# pwr.net
KiCad netlist of a schematic drawn in EAGLE
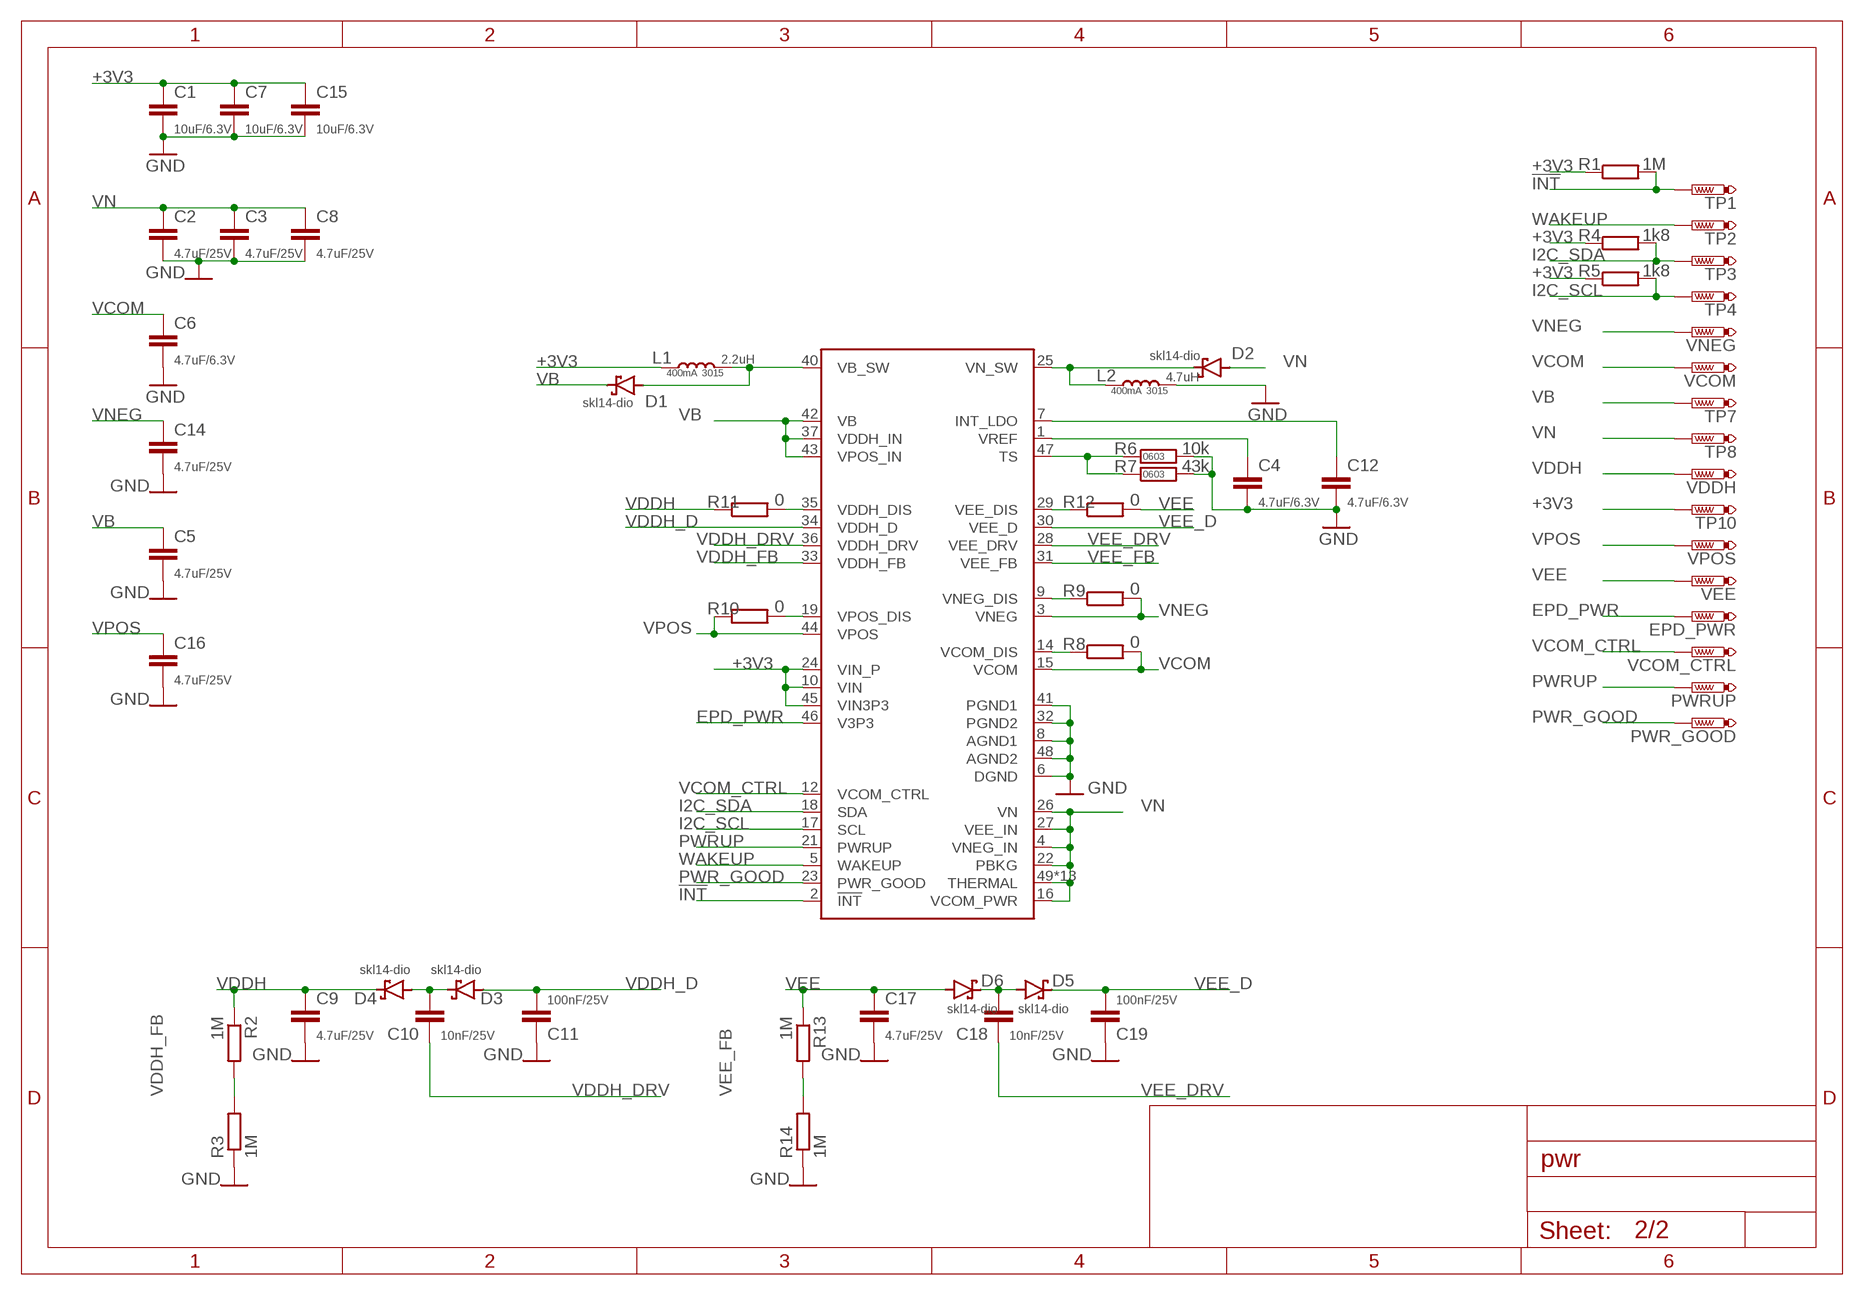
[diagram p0: schematic, sheet 2]

(export (version "E")
  (design (tool "Eeschema 10.0.6"))
  (components
    (comp (ref "C1")
      (value "10uF/6.3V")
      (footprint "eagle-import:C0805")
      (libsource (lib "eagle-import") (part "C-EUC0805"))
    )
    (comp (ref "C2")
      (value "4.7uF/25V")
      (footprint "eagle-import:C0805")
      (libsource (lib "eagle-import") (part "C-EUC0805"))
    )
    (comp (ref "C3")
      (value "4.7uF/25V")
      (footprint "eagle-import:C0805")
      (libsource (lib "eagle-import") (part "C-EUC0805"))
    )
    (comp (ref "C4")
      (value "4.7uF/6.3V")
      (footprint "eagle-import:C0603")
      (libsource (lib "eagle-import") (part "C-EUC0603"))
    )
    (comp (ref "C5")
      (value "4.7uF/25V")
      (footprint "eagle-import:C0805")
      (libsource (lib "eagle-import") (part "C-EUC0805"))
    )
    (comp (ref "C6")
      (value "4.7uF/6.3V")
      (footprint "eagle-import:C0603")
      (libsource (lib "eagle-import") (part "C-EUC0603"))
    )
    (comp (ref "C7")
      (value "10uF/6.3V")
      (footprint "eagle-import:C0805")
      (libsource (lib "eagle-import") (part "C-EUC0805"))
    )
    (comp (ref "C8")
      (value "4.7uF/25V")
      (footprint "eagle-import:C0805")
      (libsource (lib "eagle-import") (part "C-EUC0805"))
    )
    (comp (ref "C9")
      (value "4.7uF/25V")
      (footprint "eagle-import:C0805")
      (libsource (lib "eagle-import") (part "C-EUC0805"))
    )
    (comp (ref "C10")
      (value "10nF/25V")
      (footprint "eagle-import:C0402")
      (libsource (lib "eagle-import") (part "C-EUC0402"))
    )
    (comp (ref "C11")
      (value "100nF/25V")
      (footprint "eagle-import:C0603")
      (libsource (lib "eagle-import") (part "C-EUC0603"))
    )
    (comp (ref "C12")
      (value "4.7uF/6.3V")
      (footprint "eagle-import:C0603")
      (libsource (lib "eagle-import") (part "C-EUC0603"))
    )
    (comp (ref "C14")
      (value "4.7uF/25V")
      (footprint "eagle-import:C0805")
      (libsource (lib "eagle-import") (part "C-EUC0805"))
    )
    (comp (ref "C15")
      (value "10uF/6.3V")
      (footprint "eagle-import:C0805")
      (libsource (lib "eagle-import") (part "C-EUC0805"))
    )
    (comp (ref "C16")
      (value "4.7uF/25V")
      (footprint "eagle-import:C0805")
      (libsource (lib "eagle-import") (part "C-EUC0805"))
    )
    (comp (ref "C17")
      (value "4.7uF/25V")
      (footprint "eagle-import:C0805")
      (libsource (lib "eagle-import") (part "C-EUC0805"))
    )
    (comp (ref "C18")
      (value "10nF/25V")
      (footprint "eagle-import:C0402")
      (libsource (lib "eagle-import") (part "C-EUC0402"))
    )
    (comp (ref "C19")
      (value "100nF/25V")
      (footprint "eagle-import:C0603")
      (libsource (lib "eagle-import") (part "C-EUC0603"))
    )
    (comp (ref "D1")
      (value "skl14-dio")
      (footprint "eagle-import:SODFL3718X130")
      (libsource (lib "eagle-import") (part "SKL14"))
    )
    (comp (ref "D2")
      (value "skl14-dio")
      (footprint "eagle-import:SODFL3718X130")
      (libsource (lib "eagle-import") (part "SKL14"))
    )
    (comp (ref "D3")
      (value "skl14-dio")
      (footprint "eagle-import:SODFL3718X130")
      (libsource (lib "eagle-import") (part "SKL14"))
    )
    (comp (ref "D4")
      (value "skl14-dio")
      (footprint "eagle-import:SODFL3718X130")
      (libsource (lib "eagle-import") (part "SKL14"))
    )
    (comp (ref "D5")
      (value "skl14-dio")
      (footprint "eagle-import:SODFL3718X130")
      (libsource (lib "eagle-import") (part "SKL14"))
    )
    (comp (ref "D6")
      (value "skl14-dio")
      (footprint "eagle-import:SODFL3718X130")
      (libsource (lib "eagle-import") (part "SKL14"))
    )
    (comp (ref "EPD_PWR")
      (value "PTR1B1,27")
      (footprint "eagle-import:B1,27")
      (libsource (lib "eagle-import") (part "PTR1B1,27"))
    )
    (comp (ref "L1")
      (value "2.2uH")
      (footprint "eagle-import:L3230M")
      (fields (field (name "PACKAGE") "3015") (field (name "CURRENT") "400mA"))
      (libsource (lib "eagle-import") (part "DJNR3015"))
    )
    (comp (ref "L2")
      (value "4.7uH")
      (footprint "eagle-import:L3230M")
      (fields (field (name "PACKAGE") "3015") (field (name "CURRENT") "400mA"))
      (libsource (lib "eagle-import") (part "DJNR3015"))
    )
    (comp (ref "PWRUP")
      (value "PTR1B1,27")
      (footprint "eagle-import:B1,27")
      (libsource (lib "eagle-import") (part "PTR1B1,27"))
    )
    (comp (ref "PWR_GOOD")
      (value "PTR1B1,27")
      (footprint "eagle-import:B1,27")
      (libsource (lib "eagle-import") (part "PTR1B1,27"))
    )
    (comp (ref "R1")
      (value "1M")
      (footprint "eagle-import:R0603")
      (libsource (lib "eagle-import") (part "R-EU_R0603"))
    )
    (comp (ref "R2")
      (value "1M")
      (footprint "eagle-import:R0603")
      (libsource (lib "eagle-import") (part "R-EU_R0603"))
    )
    (comp (ref "R3")
      (value "1M")
      (footprint "eagle-import:R0603")
      (libsource (lib "eagle-import") (part "R-EU_R0603"))
    )
    (comp (ref "R4")
      (value "1k8")
      (footprint "eagle-import:R0603")
      (libsource (lib "eagle-import") (part "R-EU_R0603"))
    )
    (comp (ref "R5")
      (value "1k8")
      (footprint "eagle-import:R0603")
      (libsource (lib "eagle-import") (part "R-EU_R0603"))
    )
    (comp (ref "R6")
      (value "10k")
      (footprint "eagle-import:R0603")
      (fields (field (name "PACKAGE") "0603"))
      (libsource (lib "eagle-import") (part "RES-0603"))
    )
    (comp (ref "R7")
      (value "43k")
      (footprint "eagle-import:R0603")
      (fields (field (name "PACKAGE") "0603"))
      (libsource (lib "eagle-import") (part "RES-0603"))
    )
    (comp (ref "R8")
      (value "0")
      (footprint "eagle-import:R0402")
      (libsource (lib "eagle-import") (part "R-EU_R0402"))
    )
    (comp (ref "R9")
      (value "0")
      (footprint "eagle-import:R0402")
      (libsource (lib "eagle-import") (part "R-EU_R0402"))
    )
    (comp (ref "R10")
      (value "0")
      (footprint "eagle-import:R0402")
      (libsource (lib "eagle-import") (part "R-EU_R0402"))
    )
    (comp (ref "R11")
      (value "0")
      (footprint "eagle-import:R0402")
      (libsource (lib "eagle-import") (part "R-EU_R0402"))
    )
    (comp (ref "R12")
      (value "0")
      (footprint "eagle-import:R0402")
      (libsource (lib "eagle-import") (part "R-EU_R0402"))
    )
    (comp (ref "R13")
      (value "1M")
      (footprint "eagle-import:R0603")
      (libsource (lib "eagle-import") (part "R-EU_R0603"))
    )
    (comp (ref "R14")
      (value "1M")
      (footprint "eagle-import:R0603")
      (libsource (lib "eagle-import") (part "R-EU_R0603"))
    )
    (comp (ref "TP1")
      (value "PTR1B1,27")
      (footprint "eagle-import:B1,27")
      (libsource (lib "eagle-import") (part "PTR1B1,27"))
    )
    (comp (ref "TP2")
      (value "PTR1B1,27")
      (footprint "eagle-import:B1,27")
      (libsource (lib "eagle-import") (part "PTR1B1,27"))
    )
    (comp (ref "TP3")
      (value "PTR1B1,27")
      (footprint "eagle-import:B1,27")
      (libsource (lib "eagle-import") (part "PTR1B1,27"))
    )
    (comp (ref "TP4")
      (value "PTR1B1,27")
      (footprint "eagle-import:B1,27")
      (libsource (lib "eagle-import") (part "PTR1B1,27"))
    )
    (comp (ref "TP7")
      (value "PTR1B1,27")
      (footprint "eagle-import:B1,27")
      (libsource (lib "eagle-import") (part "PTR1B1,27"))
    )
    (comp (ref "TP8")
      (value "PTR1B1,27")
      (footprint "eagle-import:B1,27")
      (libsource (lib "eagle-import") (part "PTR1B1,27"))
    )
    (comp (ref "TP10")
      (value "PTR1B1,27")
      (footprint "eagle-import:B1,27")
      (libsource (lib "eagle-import") (part "PTR1B1,27"))
    )
    (comp (ref "U1")
      (value "TPS65185")
      (footprint "eagle-import:QFN50P700X700X100-49T410")
      (libsource (lib "eagle-import") (part "TPS65185"))
    )
    (comp (ref "VCOM")
      (value "PTR1B1,27")
      (footprint "eagle-import:B1,27")
      (libsource (lib "eagle-import") (part "PTR1B1,27"))
    )
    (comp (ref "VCOM_CTRL")
      (value "PTR1B1,27")
      (footprint "eagle-import:B1,27")
      (libsource (lib "eagle-import") (part "PTR1B1,27"))
    )
    (comp (ref "VDDH")
      (value "PTR1B1,27")
      (footprint "eagle-import:B1,27")
      (libsource (lib "eagle-import") (part "PTR1B1,27"))
    )
    (comp (ref "VEE")
      (value "PTR1B1,27")
      (footprint "eagle-import:B1,27")
      (libsource (lib "eagle-import") (part "PTR1B1,27"))
    )
    (comp (ref "VNEG")
      (value "PTR1B1,27")
      (footprint "eagle-import:B1,27")
      (libsource (lib "eagle-import") (part "PTR1B1,27"))
    )
    (comp (ref "VPOS")
      (value "PTR1B1,27")
      (footprint "eagle-import:B1,27")
      (libsource (lib "eagle-import") (part "PTR1B1,27"))
    )
  )
  (nets
    (net (code "1") (name "+3V3") (class "Default")
      (node (ref "C1") (pin "1") (pinfunction "1_1") (pintype "passive"))
      (node (ref "C15") (pin "1") (pinfunction "1_1") (pintype "passive"))
      (node (ref "C7") (pin "1") (pinfunction "1_1") (pintype "passive"))
      (node (ref "L1") (pin "1") (pinfunction "1_1") (pintype "passive"))
      (node (ref "R1") (pin "1") (pinfunction "1_1") (pintype "passive"))
      (node (ref "R4") (pin "1") (pinfunction "1_1") (pintype "passive"))
      (node (ref "R5") (pin "1") (pinfunction "1_1") (pintype "passive"))
      (node (ref "TP10") (pin "TP") (pinfunction "TP_TP") (pintype "input"))
      (node (ref "U1") (pin "10") (pinfunction "VIN_10") (pintype "bidirectional"))
      (node (ref "U1") (pin "24") (pinfunction "VIN_P_24") (pintype "bidirectional"))
      (node (ref "U1") (pin "45") (pinfunction "VIN3P3_45") (pintype "bidirectional"))
    )
    (net (code "2") (name "EPD_PWR") (class "Default")
      (node (ref "EPD_PWR") (pin "TP") (pinfunction "TP_TP") (pintype "input"))
      (node (ref "U1") (pin "46") (pinfunction "V3P3_46") (pintype "bidirectional"))
    )
    (net (code "3") (name "GND") (class "Default")
      (node (ref "C1") (pin "2") (pinfunction "2_2") (pintype "passive"))
      (node (ref "C11") (pin "2") (pinfunction "2_2") (pintype "passive"))
      (node (ref "C12") (pin "2") (pinfunction "2_2") (pintype "passive"))
      (node (ref "C14") (pin "2") (pinfunction "2_2") (pintype "passive"))
      (node (ref "C15") (pin "2") (pinfunction "2_2") (pintype "passive"))
      (node (ref "C16") (pin "2") (pinfunction "2_2") (pintype "passive"))
      (node (ref "C17") (pin "2") (pinfunction "2_2") (pintype "passive"))
      (node (ref "C19") (pin "2") (pinfunction "2_2") (pintype "passive"))
      (node (ref "C2") (pin "2") (pinfunction "2_2") (pintype "passive"))
      (node (ref "C3") (pin "2") (pinfunction "2_2") (pintype "passive"))
      (node (ref "C4") (pin "2") (pinfunction "2_2") (pintype "passive"))
      (node (ref "C5") (pin "2") (pinfunction "2_2") (pintype "passive"))
      (node (ref "C6") (pin "2") (pinfunction "2_2") (pintype "passive"))
      (node (ref "C7") (pin "2") (pinfunction "2_2") (pintype "passive"))
      (node (ref "C8") (pin "2") (pinfunction "2_2") (pintype "passive"))
      (node (ref "C9") (pin "2") (pinfunction "2_2") (pintype "passive"))
      (node (ref "L2") (pin "2") (pinfunction "2_2") (pintype "passive"))
      (node (ref "R14") (pin "1") (pinfunction "1_1") (pintype "passive"))
      (node (ref "R3") (pin "1") (pinfunction "1_1") (pintype "passive"))
      (node (ref "R6") (pin "2") (pinfunction "2_2") (pintype "passive"))
      (node (ref "R7") (pin "2") (pinfunction "2_2") (pintype "passive"))
      (node (ref "U1") (pin "32") (pinfunction "PGND2_32") (pintype "bidirectional"))
      (node (ref "U1") (pin "41") (pinfunction "PGND1_41") (pintype "bidirectional"))
      (node (ref "U1") (pin "48") (pinfunction "AGND2_48") (pintype "bidirectional"))
      (node (ref "U1") (pin "6") (pinfunction "DGND_6") (pintype "bidirectional"))
      (node (ref "U1") (pin "8") (pinfunction "AGND1_8") (pintype "bidirectional"))
    )
    (net (code "4") (name "I2C_SCL") (class "Default")
      (node (ref "R5") (pin "2") (pinfunction "2_2") (pintype "passive"))
      (node (ref "TP4") (pin "TP") (pinfunction "TP_TP") (pintype "input"))
      (node (ref "U1") (pin "17") (pinfunction "SCL_17") (pintype "bidirectional"))
    )
    (net (code "5") (name "I2C_SDA") (class "Default")
      (node (ref "R4") (pin "2") (pinfunction "2_2") (pintype "passive"))
      (node (ref "TP3") (pin "TP") (pinfunction "TP_TP") (pintype "input"))
      (node (ref "U1") (pin "18") (pinfunction "SDA_18") (pintype "bidirectional"))
    )
    (net (code "6") (name "Net-(C10-Pad1)") (class "Default")
      (node (ref "C10") (pin "1") (pinfunction "1_1") (pintype "passive"))
      (node (ref "D3") (pin "C") (pinfunction "C_C") (pintype "passive"))
      (node (ref "D4") (pin "A") (pinfunction "A_A") (pintype "passive"))
    )
    (net (code "7") (name "Net-(C18-Pad1)") (class "Default")
      (node (ref "C18") (pin "1") (pinfunction "1_1") (pintype "passive"))
      (node (ref "D5") (pin "A") (pinfunction "A_A") (pintype "passive"))
      (node (ref "D6") (pin "C") (pinfunction "C_C") (pintype "passive"))
    )
    (net (code "8") (name "Net-(U1-INT_LDO)") (class "Default")
      (node (ref "C12") (pin "1") (pinfunction "1_1") (pintype "passive"))
      (node (ref "U1") (pin "7") (pinfunction "INT_LDO_7") (pintype "bidirectional"))
    )
    (net (code "9") (name "Net-(U1-TS)") (class "Default")
      (node (ref "R6") (pin "1") (pinfunction "1_1") (pintype "passive"))
      (node (ref "R7") (pin "1") (pinfunction "1_1") (pintype "passive"))
      (node (ref "U1") (pin "47") (pinfunction "TS_47") (pintype "bidirectional"))
    )
    (net (code "10") (name "Net-(U1-VB_SW)") (class "Default")
      (node (ref "D1") (pin "A") (pinfunction "A_A") (pintype "passive"))
      (node (ref "L1") (pin "2") (pinfunction "2_2") (pintype "passive"))
      (node (ref "U1") (pin "40") (pinfunction "VB_SW_40") (pintype "bidirectional"))
    )
    (net (code "11") (name "Net-(U1-VCOM_DIS)") (class "Default")
      (node (ref "R8") (pin "1") (pinfunction "1_1") (pintype "passive"))
      (node (ref "U1") (pin "14") (pinfunction "VCOM_DIS_14") (pintype "bidirectional"))
    )
    (net (code "12") (name "Net-(U1-VDDH_DIS)") (class "Default")
      (node (ref "R11") (pin "2") (pinfunction "2_2") (pintype "passive"))
      (node (ref "U1") (pin "35") (pinfunction "VDDH_DIS_35") (pintype "bidirectional"))
    )
    (net (code "13") (name "Net-(U1-VEE_DIS)") (class "Default")
      (node (ref "R12") (pin "1") (pinfunction "1_1") (pintype "passive"))
      (node (ref "U1") (pin "29") (pinfunction "VEE_DIS_29") (pintype "bidirectional"))
    )
    (net (code "14") (name "Net-(U1-VNEG_DIS)") (class "Default")
      (node (ref "R9") (pin "1") (pinfunction "1_1") (pintype "passive"))
      (node (ref "U1") (pin "9") (pinfunction "VNEG_DIS_9") (pintype "bidirectional"))
    )
    (net (code "15") (name "Net-(U1-VN_SW)") (class "Default")
      (node (ref "D2") (pin "C") (pinfunction "C_C") (pintype "passive"))
      (node (ref "L2") (pin "1") (pinfunction "1_1") (pintype "passive"))
      (node (ref "U1") (pin "25") (pinfunction "VN_SW_25") (pintype "bidirectional"))
    )
    (net (code "16") (name "Net-(U1-VPOS_DIS)") (class "Default")
      (node (ref "R10") (pin "2") (pinfunction "2_2") (pintype "passive"))
      (node (ref "U1") (pin "19") (pinfunction "VPOS_DIS_19") (pintype "bidirectional"))
    )
    (net (code "17") (name "Net-(U1-VREF)") (class "Default")
      (node (ref "C4") (pin "1") (pinfunction "1_1") (pintype "passive"))
      (node (ref "U1") (pin "1") (pinfunction "VREF_1") (pintype "bidirectional"))
    )
    (net (code "18") (name "PWRUP") (class "Default")
      (node (ref "PWRUP") (pin "TP") (pinfunction "TP_TP") (pintype "input"))
      (node (ref "U1") (pin "21") (pinfunction "PWRUP_21") (pintype "bidirectional"))
    )
    (net (code "19") (name "PWR_GOOD") (class "Default")
      (node (ref "PWR_GOOD") (pin "TP") (pinfunction "TP_TP") (pintype "input"))
      (node (ref "U1") (pin "23") (pinfunction "PWR_GOOD_23") (pintype "bidirectional"))
    )
    (net (code "20") (name "VB") (class "Default")
      (node (ref "C5") (pin "1") (pinfunction "1_1") (pintype "passive"))
      (node (ref "D1") (pin "C") (pinfunction "C_C") (pintype "passive"))
      (node (ref "TP7") (pin "TP") (pinfunction "TP_TP") (pintype "input"))
      (node (ref "U1") (pin "37") (pinfunction "VDDH_IN_37") (pintype "bidirectional"))
      (node (ref "U1") (pin "42") (pinfunction "VB_42") (pintype "bidirectional"))
      (node (ref "U1") (pin "43") (pinfunction "VPOS_IN_43") (pintype "bidirectional"))
    )
    (net (code "21") (name "VCOM") (class "Default")
      (node (ref "C6") (pin "1") (pinfunction "1_1") (pintype "passive"))
      (node (ref "R8") (pin "2") (pinfunction "2_2") (pintype "passive"))
      (node (ref "U1") (pin "15") (pinfunction "VCOM_15") (pintype "bidirectional"))
      (node (ref "VCOM") (pin "TP") (pinfunction "TP_TP") (pintype "input"))
    )
    (net (code "22") (name "VCOM_CTRL") (class "Default")
      (node (ref "U1") (pin "12") (pinfunction "VCOM_CTRL_12") (pintype "bidirectional"))
      (node (ref "VCOM_CTRL") (pin "TP") (pinfunction "TP_TP") (pintype "input"))
    )
    (net (code "23") (name "VDDH") (class "Default")
      (node (ref "C9") (pin "1") (pinfunction "1_1") (pintype "passive"))
      (node (ref "D4") (pin "C") (pinfunction "C_C") (pintype "passive"))
      (node (ref "R11") (pin "1") (pinfunction "1_1") (pintype "passive"))
      (node (ref "R2") (pin "1") (pinfunction "1_1") (pintype "passive"))
      (node (ref "VDDH") (pin "TP") (pinfunction "TP_TP") (pintype "input"))
    )
    (net (code "24") (name "VDDH_D") (class "Default")
      (node (ref "C11") (pin "1") (pinfunction "1_1") (pintype "passive"))
      (node (ref "D3") (pin "A") (pinfunction "A_A") (pintype "passive"))
      (node (ref "U1") (pin "34") (pinfunction "VDDH_D_34") (pintype "bidirectional"))
    )
    (net (code "25") (name "VDDH_DRV") (class "Default")
      (node (ref "C10") (pin "2") (pinfunction "2_2") (pintype "passive"))
      (node (ref "U1") (pin "36") (pinfunction "VDDH_DRV_36") (pintype "bidirectional"))
    )
    (net (code "26") (name "VDDH_FB") (class "Default")
      (node (ref "R2") (pin "2") (pinfunction "2_2") (pintype "passive"))
      (node (ref "R3") (pin "2") (pinfunction "2_2") (pintype "passive"))
      (node (ref "U1") (pin "33") (pinfunction "VDDH_FB_33") (pintype "bidirectional"))
    )
    (net (code "27") (name "VEE") (class "Default")
      (node (ref "C17") (pin "1") (pinfunction "1_1") (pintype "passive"))
      (node (ref "D6") (pin "A") (pinfunction "A_A") (pintype "passive"))
      (node (ref "R12") (pin "2") (pinfunction "2_2") (pintype "passive"))
      (node (ref "R13") (pin "1") (pinfunction "1_1") (pintype "passive"))
      (node (ref "VEE") (pin "TP") (pinfunction "TP_TP") (pintype "input"))
    )
    (net (code "28") (name "VEE_D") (class "Default")
      (node (ref "C19") (pin "1") (pinfunction "1_1") (pintype "passive"))
      (node (ref "D5") (pin "C") (pinfunction "C_C") (pintype "passive"))
      (node (ref "U1") (pin "30") (pinfunction "VEE_D_30") (pintype "bidirectional"))
    )
    (net (code "29") (name "VEE_DRV") (class "Default")
      (node (ref "C18") (pin "2") (pinfunction "2_2") (pintype "passive"))
      (node (ref "U1") (pin "28") (pinfunction "VEE_DRV_28") (pintype "bidirectional"))
    )
    (net (code "30") (name "VEE_FB") (class "Default")
      (node (ref "R13") (pin "2") (pinfunction "2_2") (pintype "passive"))
      (node (ref "R14") (pin "2") (pinfunction "2_2") (pintype "passive"))
      (node (ref "U1") (pin "31") (pinfunction "VEE_FB_31") (pintype "bidirectional"))
    )
    (net (code "31") (name "VN") (class "Default")
      (node (ref "C2") (pin "1") (pinfunction "1_1") (pintype "passive"))
      (node (ref "C3") (pin "1") (pinfunction "1_1") (pintype "passive"))
      (node (ref "C8") (pin "1") (pinfunction "1_1") (pintype "passive"))
      (node (ref "D2") (pin "A") (pinfunction "A_A") (pintype "passive"))
      (node (ref "TP8") (pin "TP") (pinfunction "TP_TP") (pintype "input"))
      (node (ref "U1") (pin "16") (pinfunction "VCOM_PWR_16") (pintype "bidirectional"))
      (node (ref "U1") (pin "22") (pinfunction "PBKG_22") (pintype "bidirectional"))
      (node (ref "U1") (pin "26") (pinfunction "VN_26") (pintype "bidirectional"))
      (node (ref "U1") (pin "27") (pinfunction "VEE_IN_27") (pintype "bidirectional"))
      (node (ref "U1") (pin "4") (pinfunction "VNEG_IN_4") (pintype "bidirectional"))
      (node (ref "U1") (pin "49") (pinfunction "THERMAL_49") (pintype "bidirectional"))
      (node (ref "U1") (pin "P$1") (pinfunction "THERMAL_P$1") (pintype "bidirectional"))
      (node (ref "U1") (pin "P$10") (pinfunction "THERMAL_P$10") (pintype "bidirectional"))
      (node (ref "U1") (pin "P$11") (pinfunction "THERMAL_P$11") (pintype "bidirectional"))
      (node (ref "U1") (pin "P$12") (pinfunction "THERMAL_P$12") (pintype "bidirectional"))
      (node (ref "U1") (pin "P$2") (pinfunction "THERMAL_P$2") (pintype "bidirectional"))
      (node (ref "U1") (pin "P$3") (pinfunction "THERMAL_P$3") (pintype "bidirectional"))
      (node (ref "U1") (pin "P$4") (pinfunction "THERMAL_P$4") (pintype "bidirectional"))
      (node (ref "U1") (pin "P$5") (pinfunction "THERMAL_P$5") (pintype "bidirectional"))
      (node (ref "U1") (pin "P$6") (pinfunction "THERMAL_P$6") (pintype "bidirectional"))
      (node (ref "U1") (pin "P$7") (pinfunction "THERMAL_P$7") (pintype "bidirectional"))
      (node (ref "U1") (pin "P$8") (pinfunction "THERMAL_P$8") (pintype "bidirectional"))
      (node (ref "U1") (pin "P$9") (pinfunction "THERMAL_P$9") (pintype "bidirectional"))
    )
    (net (code "32") (name "VNEG") (class "Default")
      (node (ref "C14") (pin "1") (pinfunction "1_1") (pintype "passive"))
      (node (ref "R9") (pin "2") (pinfunction "2_2") (pintype "passive"))
      (node (ref "U1") (pin "3") (pinfunction "VNEG_3") (pintype "bidirectional"))
      (node (ref "VNEG") (pin "TP") (pinfunction "TP_TP") (pintype "input"))
    )
    (net (code "33") (name "VPOS") (class "Default")
      (node (ref "C16") (pin "1") (pinfunction "1_1") (pintype "passive"))
      (node (ref "R10") (pin "1") (pinfunction "1_1") (pintype "passive"))
      (node (ref "U1") (pin "44") (pinfunction "VPOS_44") (pintype "bidirectional"))
      (node (ref "VPOS") (pin "TP") (pinfunction "TP_TP") (pintype "input"))
    )
    (net (code "34") (name "WAKEUP") (class "Default")
      (node (ref "TP2") (pin "TP") (pinfunction "TP_TP") (pintype "input"))
      (node (ref "U1") (pin "5") (pinfunction "WAKEUP_5") (pintype "bidirectional"))
    )
    (net (code "35") (name "~{INT}") (class "Default")
      (node (ref "R1") (pin "2") (pinfunction "2_2") (pintype "passive"))
      (node (ref "TP1") (pin "TP") (pinfunction "TP_TP") (pintype "input"))
      (node (ref "U1") (pin "2") (pinfunction "~{INT}_2") (pintype "bidirectional"))
    )
  )
)
